# Puzzle-Encoder_v1_1.net
KiCad netlist of a schematic drawn in EAGLE
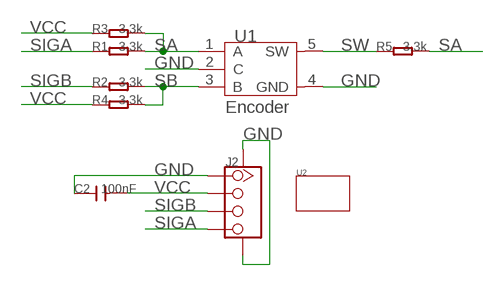
[diagram p0: schematic, sheet 1]

(export (version "E")
  (design (tool "Eeschema 10.0.6"))
  (components
    (comp (ref "C2")
      (value "100nF")
      (footprint "eagle-import:C0603")
      (libsource (lib "eagle-import") (part "C-0603"))
    )
    (comp (ref "J2")
      (value "TWIG-4P-2.0-SMD-FEMALE-REINFORCE'DD'")
      (footprint "eagle-import:4P-SMD-2.0")
      (libsource (lib "eagle-import") (part "TWIG-4P-2.0-SMD-FEMALE-REINFORCE'DD'"))
    )
    (comp (ref "R1")
      (value "3.3k")
      (footprint "eagle-import:R0603")
      (libsource (lib "eagle-import") (part "R-0603"))
    )
    (comp (ref "R2")
      (value "3.3k")
      (footprint "eagle-import:R0603")
      (libsource (lib "eagle-import") (part "R-0603"))
    )
    (comp (ref "R3")
      (value "3.3k")
      (footprint "eagle-import:R0603")
      (libsource (lib "eagle-import") (part "R-0603"))
    )
    (comp (ref "R4")
      (value "3.3k")
      (footprint "eagle-import:R0603")
      (libsource (lib "eagle-import") (part "R-0603"))
    )
    (comp (ref "R5")
      (value "3.3k")
      (footprint "eagle-import:R0603")
      (libsource (lib "eagle-import") (part "R-0603"))
    )
    (comp (ref "U1")
      (value "Encoder")
      (footprint "eagle-import:5P-13.75X11.7X6.5H")
      (libsource (lib "eagle-import") (part "ROTARY-ENCODE-5P"))
    )
    (comp (ref "U2")
      (value "TWIG'1U'")
      (footprint "eagle-import:1U-DIM-W_-DRILL")
      (libsource (lib "eagle-import") (part "TWIG'1U'"))
    )
  )
  (nets
    (net (code "1") (name "/GND") (class "Default")
      (node (ref "C2") (pin "1") (pinfunction "1_1") (pintype "passive"))
      (node (ref "J2") (pin "1") (pinfunction "1_1") (pintype "bidirectional"))
      (node (ref "J2") (pin "SS1") (pinfunction "SS1_SS1") (pintype "bidirectional"))
      (node (ref "J2") (pin "SS2") (pinfunction "SS2_SS2") (pintype "bidirectional"))
      (node (ref "U1") (pin "2") (pinfunction "C_2") (pintype "bidirectional"))
      (node (ref "U1") (pin "4") (pinfunction "GND_4") (pintype "bidirectional"))
    )
    (net (code "2") (name "/SA") (class "Default")
      (node (ref "R1") (pin "2") (pinfunction "2_2") (pintype "passive"))
      (node (ref "R3") (pin "2") (pinfunction "2_2") (pintype "passive"))
      (node (ref "R5") (pin "2") (pinfunction "2_2") (pintype "passive"))
      (node (ref "U1") (pin "1") (pinfunction "A_1") (pintype "bidirectional"))
    )
    (net (code "3") (name "/SB") (class "Default")
      (node (ref "R2") (pin "2") (pinfunction "2_2") (pintype "passive"))
      (node (ref "R4") (pin "2") (pinfunction "2_2") (pintype "passive"))
      (node (ref "U1") (pin "3") (pinfunction "B_3") (pintype "bidirectional"))
    )
    (net (code "4") (name "/SIGA") (class "Default")
      (node (ref "J2") (pin "4") (pinfunction "4_4") (pintype "bidirectional"))
      (node (ref "R1") (pin "1") (pinfunction "1_1") (pintype "passive"))
    )
    (net (code "5") (name "/SIGB") (class "Default")
      (node (ref "J2") (pin "3") (pinfunction "3_3") (pintype "bidirectional"))
      (node (ref "R2") (pin "1") (pinfunction "1_1") (pintype "passive"))
    )
    (net (code "6") (name "/SW") (class "Default")
      (node (ref "R5") (pin "1") (pinfunction "1_1") (pintype "passive"))
      (node (ref "U1") (pin "5") (pinfunction "SW_5") (pintype "bidirectional"))
    )
    (net (code "7") (name "/VCC") (class "Default")
      (node (ref "C2") (pin "2") (pinfunction "2_2") (pintype "passive"))
      (node (ref "J2") (pin "2") (pinfunction "2_2") (pintype "bidirectional"))
      (node (ref "R3") (pin "1") (pinfunction "1_1") (pintype "passive"))
      (node (ref "R4") (pin "1") (pinfunction "1_1") (pintype "passive"))
    )
  )
)
